# STLINKV2-1.net
KiCad netlist of a schematic drawn in Altium Designer
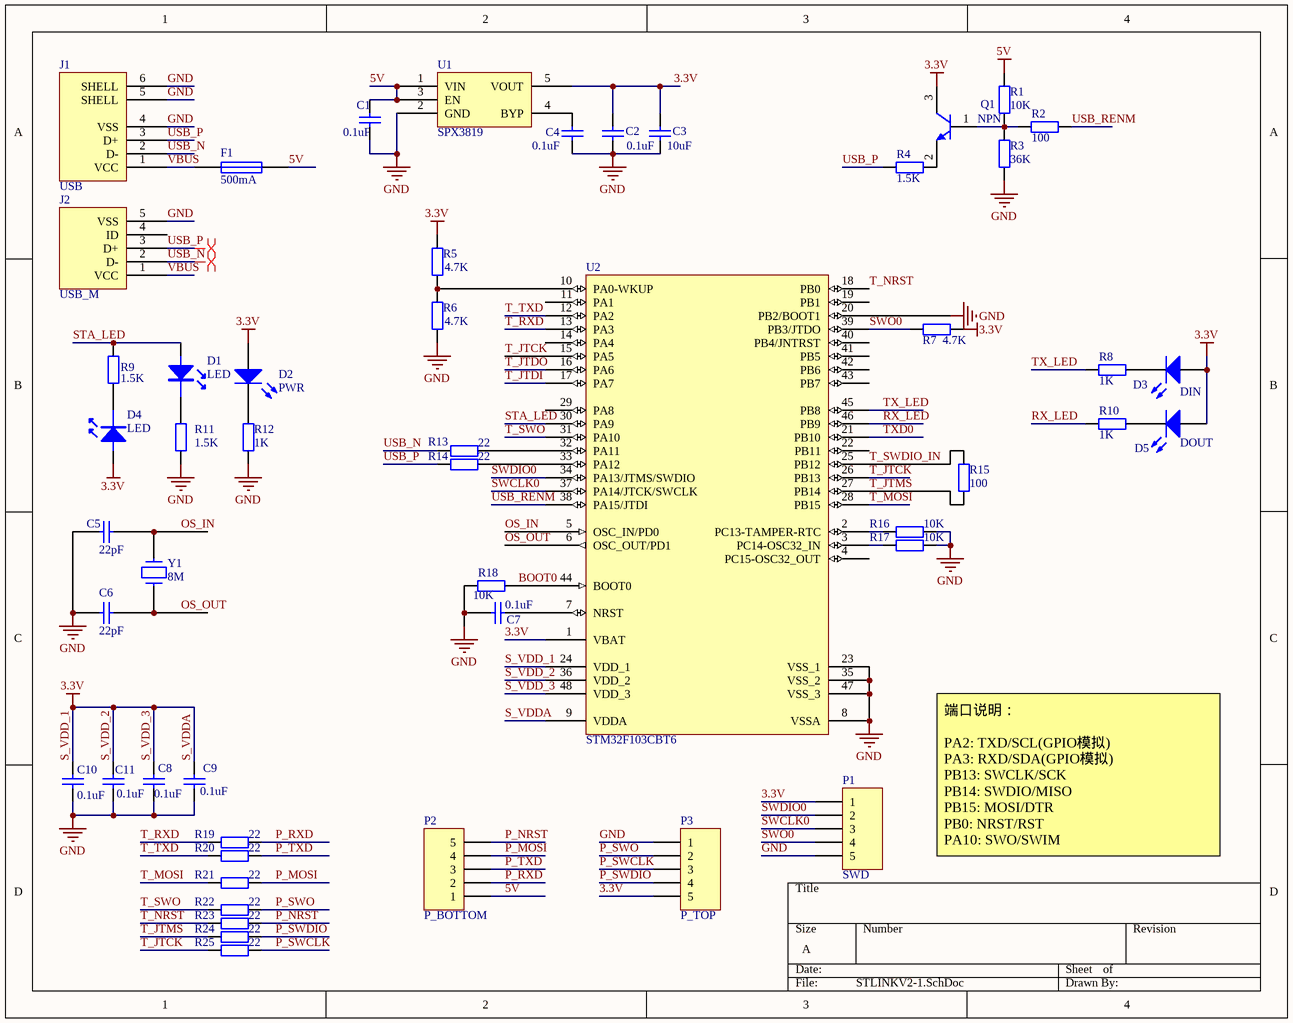
[diagram p0: STLINKV2-1.SchDoc]

(export (version "E")
  (design (tool "Eeschema 10.0.6"))
  (components
    (comp (ref "C1")
      (value "0.1uF")
      (footprint "C-0603")
      (description "Capacitor")
      (fields (field (name "Comment") "Cap") (field (name "PUBLISHER") "Altium Limited"))
      (libsource (lib "Miscellaneous Devices") (part "Cap"))
    )
    (comp (ref "C2")
      (value "0.1uF")
      (footprint "C-0603")
      (description "Capacitor")
      (fields (field (name "Comment") "Cap") (field (name "PUBLISHER") "Altium Limited"))
      (libsource (lib "Miscellaneous Devices") (part "Cap"))
    )
    (comp (ref "C3")
      (value "10uF")
      (footprint "C-0603")
      (description "Capacitor")
      (fields (field (name "Comment") "Cap") (field (name "PUBLISHER") "Altium Limited"))
      (libsource (lib "Miscellaneous Devices") (part "Cap"))
    )
    (comp (ref "C4")
      (value "0.1uF")
      (footprint "C-0603")
      (description "Capacitor")
      (fields (field (name "Comment") "Cap") (field (name "PUBLISHER") "Altium Limited"))
      (libsource (lib "Miscellaneous Devices") (part "Cap"))
    )
    (comp (ref "C5")
      (value "22pF")
      (footprint "C-0603")
      (fields (field (name "Comment") "Cap"))
      (libsource (lib "WK_PCB") (part "Cap"))
    )
    (comp (ref "C6")
      (value "22pF")
      (footprint "C-0603")
      (fields (field (name "Comment") "Cap"))
      (libsource (lib "WK_PCB") (part "Cap"))
    )
    (comp (ref "C7")
      (value "0.1uF")
      (footprint "C-0603")
      (fields (field (name "Comment") "Cap"))
      (libsource (lib "WK_PCB") (part "Cap"))
    )
    (comp (ref "C8")
      (value "0.1uF")
      (footprint "C-0603")
      (description "Capacitor")
      (fields (field (name "Comment") "Cap") (field (name "PUBLISHER") "Altium Limited"))
      (libsource (lib "Miscellaneous Devices") (part "Cap"))
    )
    (comp (ref "C9")
      (value "0.1uF")
      (footprint "C-0603")
      (description "Capacitor")
      (fields (field (name "Comment") "Cap") (field (name "PUBLISHER") "Altium Limited"))
      (libsource (lib "Miscellaneous Devices") (part "Cap"))
    )
    (comp (ref "C10")
      (value "0.1uF")
      (footprint "C-0603")
      (description "Capacitor")
      (fields (field (name "Comment") "Cap") (field (name "PUBLISHER") "Altium Limited"))
      (libsource (lib "Miscellaneous Devices") (part "Cap"))
    )
    (comp (ref "C11")
      (value "0.1uF")
      (footprint "C-0603")
      (description "Capacitor")
      (fields (field (name "Comment") "Cap") (field (name "PUBLISHER") "Altium Limited"))
      (libsource (lib "Miscellaneous Devices") (part "Cap"))
    )
    (comp (ref "D1")
      (value "LED")
      (footprint "SMT_LED_0603")
      (description "LED 发光二极管")
      (libsource (lib "WK_PCB") (part "LED"))
    )
    (comp (ref "D2")
      (value "PWR")
      (footprint "SMT_LED_0603")
      (description "Typical RED, GREEN, YELLOW, AMBER GaAs LED")
      (fields (field (name "PUBLISHER") "Altium Limited"))
      (libsource (lib "Miscellaneous Devices") (part "LED2"))
    )
    (comp (ref "D3")
      (value "DIN")
      (footprint "SMT_LED_0603")
      (description "Typical RED, GREEN, YELLOW, AMBER GaAs LED")
      (fields (field (name "PUBLISHER") "Altium Limited"))
      (libsource (lib "Miscellaneous Devices") (part "LED2"))
    )
    (comp (ref "D4")
      (value "LED")
      (footprint "SMT_LED_0603")
      (description "LED 发光二极管")
      (libsource (lib "WK_PCB") (part "LED"))
    )
    (comp (ref "D5")
      (value "DOUT")
      (footprint "SMT_LED_0603")
      (description "Typical RED, GREEN, YELLOW, AMBER GaAs LED")
      (fields (field (name "PUBLISHER") "Altium Limited"))
      (libsource (lib "Miscellaneous Devices") (part "LED2"))
    )
    (comp (ref "F1")
      (value "500mA")
      (footprint "0805-1")
      (description "保险丝")
      (fields (field (name "Comment") "Fuse1"))
      (libsource (lib "Fszhang") (part "Fuse1"))
    )
    (comp (ref "J1")
      (value "USB")
      (footprint "USB-B")
      (description "USB接口")
      (libsource (lib "HDR_Fszhang") (part "USB"))
    )
    (comp (ref "J2")
      (value "USB_M")
      (footprint "USB_MICRO_5S_B")
      (description "Micro/Mini USB")
      (libsource (lib "HDR_Fszhang") (part "USB_M"))
    )
    (comp (ref "P1")
      (value "SWD")
      (footprint "SIP5-1.27")
      (description "Header, 5-Pin")
      (fields (field (name "PUBLISHER") "Altium Limited"))
      (libsource (lib "") (part "Header 5_1"))
    )
    (comp (ref "P2")
      (value "P_BOTTOM")
      (footprint "HEADER 5")
      (description "Header, 5-Pin")
      (fields (field (name "PUBLISHER") "Altium Limited"))
      (libsource (lib "Miscellaneous Connectors") (part "Header 5"))
    )
    (comp (ref "P3")
      (value "P_TOP")
      (footprint "HEADER 5")
      (description "Header, 5-Pin")
      (fields (field (name "PUBLISHER") "Altium Limited"))
      (libsource (lib "") (part "Header 5_1"))
    )
    (comp (ref "Q1")
      (value "NPN")
      (footprint "SOT23-3")
      (description "贴片三极管")
      (fields (field (name "PUBLISHER") "Altium Limited"))
      (libsource (lib "Fszhang") (part "NPN1"))
    )
    (comp (ref "R1")
      (value "10K")
      (footprint "0603-1")
      (description "贴片电阻")
      (fields (field (name "Comment") "Res1") (field (name "PUBLISHER") "Altium Limited"))
      (libsource (lib "Fszhang") (part "Res1"))
    )
    (comp (ref "R2")
      (value "100")
      (footprint "0603-1")
      (description "贴片电阻")
      (fields (field (name "Comment") "Res1") (field (name "PUBLISHER") "Altium Limited"))
      (libsource (lib "") (part "Res1_1"))
    )
    (comp (ref "R3")
      (value "36K")
      (footprint "0603-1")
      (description "贴片电阻")
      (fields (field (name "Comment") "Res1") (field (name "PUBLISHER") "Altium Limited"))
      (libsource (lib "Fszhang") (part "Res1"))
    )
    (comp (ref "R4")
      (value "1.5K")
      (footprint "0603-1")
      (description "贴片电阻")
      (fields (field (name "Comment") "Res1") (field (name "PUBLISHER") "Altium Limited"))
      (libsource (lib "") (part "Res1_2"))
    )
    (comp (ref "R5")
      (value "4.7K")
      (footprint "0603-1")
      (description "Resistor")
      (fields (field (name "Comment") "Res2") (field (name "PUBLISHER") "Altium Limited"))
      (libsource (lib "") (part "Res2_1"))
    )
    (comp (ref "R6")
      (value "4.7K")
      (footprint "0603-1")
      (description "Resistor")
      (fields (field (name "Comment") "Res2") (field (name "PUBLISHER") "Altium Limited"))
      (libsource (lib "") (part "Res2_1"))
    )
    (comp (ref "R7")
      (value "4.7K")
      (footprint "0603-1")
      (description "Resistor")
      (fields (field (name "Comment") "Res2") (field (name "PUBLISHER") "Altium Limited"))
      (libsource (lib "Miscellaneous Devices") (part "Res2"))
    )
    (comp (ref "R8")
      (value "1K")
      (footprint "0603-1")
      (description "Resistor")
      (fields (field (name "Comment") "Res2") (field (name "PUBLISHER") "Altium Limited"))
      (libsource (lib "Miscellaneous Devices") (part "Res2"))
    )
    (comp (ref "R9")
      (value "1.5K")
      (footprint "0603-1")
      (description "Resistor")
      (fields (field (name "Comment") "Res2") (field (name "PUBLISHER") "Altium Limited"))
      (libsource (lib "") (part "Res2_1"))
    )
    (comp (ref "R10")
      (value "1K")
      (footprint "0603-1")
      (description "Resistor")
      (fields (field (name "Comment") "Res2") (field (name "PUBLISHER") "Altium Limited"))
      (libsource (lib "Miscellaneous Devices") (part "Res2"))
    )
    (comp (ref "R11")
      (value "1.5K")
      (footprint "0603-1")
      (description "Resistor")
      (fields (field (name "Comment") "Res2") (field (name "PUBLISHER") "Altium Limited"))
      (libsource (lib "") (part "Res2_1"))
    )
    (comp (ref "R12")
      (value "1K")
      (footprint "0603-1")
      (description "Resistor")
      (fields (field (name "Comment") "Res2") (field (name "PUBLISHER") "Altium Limited"))
      (libsource (lib "") (part "Res2_1"))
    )
    (comp (ref "R13")
      (value "22")
      (footprint "0603-1")
      (description "Resistor")
      (fields (field (name "Comment") "Res2") (field (name "PUBLISHER") "Altium Limited"))
      (libsource (lib "Miscellaneous Devices") (part "Res2"))
    )
    (comp (ref "R14")
      (value "22")
      (footprint "0603-1")
      (description "Resistor")
      (fields (field (name "Comment") "Res2") (field (name "PUBLISHER") "Altium Limited"))
      (libsource (lib "Miscellaneous Devices") (part "Res2"))
    )
    (comp (ref "R15")
      (value "100")
      (footprint "0603-1")
      (description "Resistor")
      (fields (field (name "Comment") "Res2") (field (name "PUBLISHER") "Altium Limited"))
      (libsource (lib "") (part "Res2_1"))
    )
    (comp (ref "R16")
      (value "10K")
      (footprint "0603-1")
      (description "贴片电阻")
      (fields (field (name "Comment") "Res1") (field (name "PUBLISHER") "Altium Limited"))
      (libsource (lib "") (part "Res1_1"))
    )
    (comp (ref "R17")
      (value "10K")
      (footprint "0603-1")
      (description "贴片电阻")
      (fields (field (name "Comment") "Res1") (field (name "PUBLISHER") "Altium Limited"))
      (libsource (lib "") (part "Res1_1"))
    )
    (comp (ref "R18")
      (value "10K")
      (footprint "0603-1")
      (description "Resistor")
      (fields (field (name "Comment") "Res2") (field (name "PUBLISHER") "Altium Limited"))
      (libsource (lib "Miscellaneous Devices") (part "Res2"))
    )
    (comp (ref "R19")
      (value "22")
      (footprint "0603-1")
      (description "Resistor")
      (fields (field (name "Comment") "Res2") (field (name "PUBLISHER") "Altium Limited"))
      (libsource (lib "Miscellaneous Devices") (part "Res2"))
    )
    (comp (ref "R20")
      (value "22")
      (footprint "0603-1")
      (description "Resistor")
      (fields (field (name "Comment") "Res2") (field (name "PUBLISHER") "Altium Limited"))
      (libsource (lib "Miscellaneous Devices") (part "Res2"))
    )
    (comp (ref "R21")
      (value "22")
      (footprint "0603-1")
      (description "Resistor")
      (fields (field (name "Comment") "Res2") (field (name "PUBLISHER") "Altium Limited"))
      (libsource (lib "Miscellaneous Devices") (part "Res2"))
    )
    (comp (ref "R22")
      (value "22")
      (footprint "0603-1")
      (description "Resistor")
      (fields (field (name "Comment") "Res2") (field (name "PUBLISHER") "Altium Limited"))
      (libsource (lib "Miscellaneous Devices") (part "Res2"))
    )
    (comp (ref "R23")
      (value "22")
      (footprint "0603-1")
      (description "Resistor")
      (fields (field (name "Comment") "Res2") (field (name "PUBLISHER") "Altium Limited"))
      (libsource (lib "Miscellaneous Devices") (part "Res2"))
    )
    (comp (ref "R24")
      (value "22")
      (footprint "0603-1")
      (description "Resistor")
      (fields (field (name "Comment") "Res2") (field (name "PUBLISHER") "Altium Limited"))
      (libsource (lib "Miscellaneous Devices") (part "Res2"))
    )
    (comp (ref "R25")
      (value "22")
      (footprint "0603-1")
      (description "Resistor")
      (fields (field (name "Comment") "Res2") (field (name "PUBLISHER") "Altium Limited"))
      (libsource (lib "Miscellaneous Devices") (part "Res2"))
    )
    (comp (ref "U1") (value "SPX3819") (footprint "SOT23-5") (libsource (lib "Schlib1") (part "SPX3819")))
    (comp (ref "U2")
      (value "STM32F103CBT6")
      (footprint "LQFP48_N")
      (description "STM32 ARM-based 32-bit MCU with 64 Kbytes Flash, 48-pin LQFP, Industrial Temperature")
      (fields (field (name "PUBLISHER") "Altium Limited"))
      (libsource (lib "ST Microcontroller 32-Bit STM32") (part "STM32F103C8T6"))
    )
    (comp (ref "Y1") (value "8M") (footprint "XAL5032 2-Leads") (libsource (lib "WK_PCB") (part "XTAL")))
  )
  (nets
    (net (code "1") (name "/BOOT0") (class "Default")
      (node (ref "R18") (pin "2") (pinfunction "2_2") (pintype "passive"))
      (node (ref "U2") (pin "44") (pinfunction "BOOT0_44") (pintype "input"))
    )
    (net (code "2") (name "/OS_IN") (class "Default")
      (node (ref "C5") (pin "2") (pinfunction "2_2") (pintype "passive"))
      (node (ref "U2") (pin "5") (pinfunction "OSC_IN/PD0_5") (pintype "input"))
      (node (ref "Y1") (pin "2") (pinfunction "2_2") (pintype "passive"))
    )
    (net (code "3") (name "/OS_OUT") (class "Default")
      (node (ref "C6") (pin "2") (pinfunction "2_2") (pintype "passive"))
      (node (ref "U2") (pin "6") (pinfunction "OSC_OUT/PD1_6") (pintype "output"))
      (node (ref "Y1") (pin "1") (pinfunction "1_1") (pintype "passive"))
    )
    (net (code "4") (name "/P_MOSI") (class "Default")
      (node (ref "P2") (pin "4") (pinfunction "4_4") (pintype "passive"))
      (node (ref "R21") (pin "2") (pinfunction "2_2") (pintype "passive"))
    )
    (net (code "5") (name "/P_NRST") (class "Default")
      (node (ref "P2") (pin "5") (pinfunction "5_5") (pintype "passive"))
      (node (ref "R23") (pin "2") (pinfunction "2_2") (pintype "passive"))
    )
    (net (code "6") (name "/P_RXD") (class "Default")
      (node (ref "P2") (pin "2") (pinfunction "2_2") (pintype "passive"))
      (node (ref "R19") (pin "2") (pinfunction "2_2") (pintype "passive"))
    )
    (net (code "7") (name "/P_SWCLK") (class "Default")
      (node (ref "P3") (pin "3") (pinfunction "3_3") (pintype "passive"))
      (node (ref "R25") (pin "2") (pinfunction "2_2") (pintype "passive"))
    )
    (net (code "8") (name "/P_SWDIO") (class "Default")
      (node (ref "P3") (pin "4") (pinfunction "4_4") (pintype "passive"))
      (node (ref "R24") (pin "2") (pinfunction "2_2") (pintype "passive"))
    )
    (net (code "9") (name "/P_SWO") (class "Default")
      (node (ref "P3") (pin "2") (pinfunction "2_2") (pintype "passive"))
      (node (ref "R22") (pin "2") (pinfunction "2_2") (pintype "passive"))
    )
    (net (code "10") (name "/P_TXD") (class "Default")
      (node (ref "P2") (pin "3") (pinfunction "3_3") (pintype "passive"))
      (node (ref "R20") (pin "2") (pinfunction "2_2") (pintype "passive"))
    )
    (net (code "11") (name "/RX_LED") (class "Default")
      (node (ref "R10") (pin "1") (pinfunction "1_1") (pintype "passive"))
      (node (ref "U2") (pin "46") (pinfunction "PB9_46") (pintype "bidirectional"))
    )
    (net (code "12") (name "/STA_LED") (class "Default")
      (node (ref "D1") (pin "1") (pinfunction "A_1") (pintype "passive"))
      (node (ref "R9") (pin "2") (pinfunction "2_2") (pintype "passive"))
      (node (ref "U2") (pin "30") (pinfunction "PA9_30") (pintype "bidirectional"))
    )
    (net (code "13") (name "/SWCLK0") (class "Default")
      (node (ref "P1") (pin "3") (pinfunction "3_3") (pintype "passive"))
      (node (ref "U2") (pin "37") (pinfunction "PA14/JTCK/SWCLK_37") (pintype "bidirectional"))
    )
    (net (code "14") (name "/SWDIO0") (class "Default")
      (node (ref "P1") (pin "2") (pinfunction "2_2") (pintype "passive"))
      (node (ref "U2") (pin "34") (pinfunction "PA13/JTMS/SWDIO_34") (pintype "bidirectional"))
    )
    (net (code "15") (name "/SWO0") (class "Default")
      (node (ref "P1") (pin "4") (pinfunction "4_4") (pintype "passive"))
      (node (ref "R7") (pin "1") (pinfunction "1_1") (pintype "passive"))
      (node (ref "U2") (pin "39") (pinfunction "PB3/JTDO_39") (pintype "bidirectional"))
    )
    (net (code "16") (name "/TXD0") (class "Default")
      (node (ref "U2") (pin "21") (pinfunction "PB10_21") (pintype "bidirectional"))
    )
    (net (code "17") (name "/TX_LED") (class "Default")
      (node (ref "R8") (pin "1") (pinfunction "1_1") (pintype "passive"))
      (node (ref "U2") (pin "45") (pinfunction "PB8_45") (pintype "bidirectional"))
    )
    (net (code "18") (name "/T_JTCK") (class "Default")
      (node (ref "R25") (pin "1") (pinfunction "1_1") (pintype "passive"))
      (node (ref "U2") (pin "15") (pinfunction "PA5_15") (pintype "bidirectional"))
      (node (ref "U2") (pin "26") (pinfunction "PB13_26") (pintype "bidirectional"))
    )
    (net (code "19") (name "/T_JTDI") (class "Default")
      (node (ref "U2") (pin "17") (pinfunction "PA7_17") (pintype "bidirectional"))
    )
    (net (code "20") (name "/T_JTDO") (class "Default")
      (node (ref "U2") (pin "16") (pinfunction "PA6_16") (pintype "bidirectional"))
    )
    (net (code "21") (name "/T_JTMS") (class "Default")
      (node (ref "R15") (pin "1") (pinfunction "1_1") (pintype "passive"))
      (node (ref "R24") (pin "1") (pinfunction "1_1") (pintype "passive"))
      (node (ref "U2") (pin "27") (pinfunction "PB14_27") (pintype "bidirectional"))
    )
    (net (code "22") (name "/T_MOSI") (class "Default")
      (node (ref "R21") (pin "1") (pinfunction "1_1") (pintype "passive"))
      (node (ref "U2") (pin "28") (pinfunction "PB15_28") (pintype "bidirectional"))
    )
    (net (code "23") (name "/T_NRST") (class "Default")
      (node (ref "R23") (pin "1") (pinfunction "1_1") (pintype "passive"))
      (node (ref "U2") (pin "18") (pinfunction "PB0_18") (pintype "bidirectional"))
    )
    (net (code "24") (name "/T_RXD") (class "Default")
      (node (ref "R19") (pin "1") (pinfunction "1_1") (pintype "passive"))
      (node (ref "U2") (pin "13") (pinfunction "PA3_13") (pintype "bidirectional"))
    )
    (net (code "25") (name "/T_SWDIO_IN") (class "Default")
      (node (ref "R15") (pin "2") (pinfunction "2_2") (pintype "passive"))
      (node (ref "U2") (pin "25") (pinfunction "PB12_25") (pintype "bidirectional"))
    )
    (net (code "26") (name "/T_SWO") (class "Default")
      (node (ref "R22") (pin "1") (pinfunction "1_1") (pintype "passive"))
      (node (ref "U2") (pin "31") (pinfunction "PA10_31") (pintype "bidirectional"))
    )
    (net (code "27") (name "/T_TXD") (class "Default")
      (node (ref "R20") (pin "1") (pinfunction "1_1") (pintype "passive"))
      (node (ref "U2") (pin "12") (pinfunction "PA2_12") (pintype "bidirectional"))
    )
    (net (code "28") (name "/USB_N") (class "Default")
      (node (ref "J1") (pin "2") (pinfunction "D-_2") (pintype "passive"))
      (node (ref "J2") (pin "2") (pinfunction "D-_2") (pintype "passive"))
      (node (ref "R13") (pin "1") (pinfunction "1_1") (pintype "passive"))
    )
    (net (code "29") (name "/USB_P") (class "Default")
      (node (ref "J1") (pin "3") (pinfunction "D+_3") (pintype "passive"))
      (node (ref "J2") (pin "3") (pinfunction "D+_3") (pintype "passive"))
      (node (ref "R14") (pin "1") (pinfunction "1_1") (pintype "passive"))
      (node (ref "R4") (pin "2") (pinfunction "2_2") (pintype "passive"))
    )
    (net (code "30") (name "/USB_RENM") (class "Default")
      (node (ref "R2") (pin "2") (pinfunction "2_2") (pintype "passive"))
      (node (ref "U2") (pin "38") (pinfunction "PA15/JTDI_38") (pintype "bidirectional"))
    )
    (net (code "31") (name "/VBUS") (class "Default")
      (node (ref "F1") (pin "2") (pinfunction "2_2") (pintype "passive"))
      (node (ref "J1") (pin "1") (pinfunction "VCC_1") (pintype "passive"))
      (node (ref "J2") (pin "1") (pinfunction "VCC_1") (pintype "passive"))
    )
    (net (code "32") (name "3.3V") (class "Default")
      (node (ref "C10") (pin "2") (pinfunction "2_2") (pintype "passive"))
      (node (ref "C11") (pin "2") (pinfunction "2_2") (pintype "passive"))
      (node (ref "C2") (pin "2") (pinfunction "2_2") (pintype "passive"))
      (node (ref "C3") (pin "2") (pinfunction "2_2") (pintype "passive"))
      (node (ref "C8") (pin "2") (pinfunction "2_2") (pintype "passive"))
      (node (ref "C9") (pin "2") (pinfunction "2_2") (pintype "passive"))
      (node (ref "D2") (pin "1") (pinfunction "A_1") (pintype "passive"))
      (node (ref "D3") (pin "1") (pinfunction "A_1") (pintype "passive"))
      (node (ref "D4") (pin "1") (pinfunction "A_1") (pintype "passive"))
      (node (ref "D5") (pin "1") (pinfunction "A_1") (pintype "passive"))
      (node (ref "P1") (pin "1") (pinfunction "1_1") (pintype "passive"))
      (node (ref "P3") (pin "5") (pinfunction "5_5") (pintype "passive"))
      (node (ref "Q1") (pin "3") (pinfunction "C_3") (pintype "passive"))
      (node (ref "R5") (pin "2") (pinfunction "2_2") (pintype "passive"))
      (node (ref "R7") (pin "2") (pinfunction "2_2") (pintype "passive"))
      (node (ref "U1") (pin "5") (pinfunction "VOUT_5") (pintype "passive"))
      (node (ref "U2") (pin "1") (pinfunction "VBAT_1") (pintype "power_in"))
      (node (ref "U2") (pin "24") (pinfunction "VDD_1_24") (pintype "power_in"))
      (node (ref "U2") (pin "36") (pinfunction "VDD_2_36") (pintype "power_in"))
      (node (ref "U2") (pin "48") (pinfunction "VDD_3_48") (pintype "power_in"))
      (node (ref "U2") (pin "9") (pinfunction "VDDA_9") (pintype "power_in"))
    )
    (net (code "33") (name "5V") (class "Default")
      (node (ref "C1") (pin "2") (pinfunction "2_2") (pintype "passive"))
      (node (ref "F1") (pin "1") (pinfunction "1_1") (pintype "passive"))
      (node (ref "P2") (pin "1") (pinfunction "1_1") (pintype "passive"))
      (node (ref "R1") (pin "1") (pinfunction "1_1") (pintype "passive"))
      (node (ref "U1") (pin "1") (pinfunction "VIN_1") (pintype "passive"))
      (node (ref "U1") (pin "3") (pinfunction "EN_3") (pintype "passive"))
    )
    (net (code "34") (name "GND") (class "Default")
      (node (ref "C1") (pin "1") (pinfunction "1_1") (pintype "passive"))
      (node (ref "C10") (pin "1") (pinfunction "1_1") (pintype "passive"))
      (node (ref "C11") (pin "1") (pinfunction "1_1") (pintype "passive"))
      (node (ref "C2") (pin "1") (pinfunction "1_1") (pintype "passive"))
      (node (ref "C3") (pin "1") (pinfunction "1_1") (pintype "passive"))
      (node (ref "C4") (pin "1") (pinfunction "1_1") (pintype "passive"))
      (node (ref "C5") (pin "1") (pinfunction "1_1") (pintype "passive"))
      (node (ref "C6") (pin "1") (pinfunction "1_1") (pintype "passive"))
      (node (ref "C7") (pin "1") (pinfunction "1_1") (pintype "passive"))
      (node (ref "C8") (pin "1") (pinfunction "1_1") (pintype "passive"))
      (node (ref "C9") (pin "1") (pinfunction "1_1") (pintype "passive"))
      (node (ref "J1") (pin "4") (pinfunction "VSS_4") (pintype "passive"))
      (node (ref "J1") (pin "5") (pinfunction "SHELL_5") (pintype "passive"))
      (node (ref "J1") (pin "6") (pinfunction "SHELL_6") (pintype "passive"))
      (node (ref "J2") (pin "5") (pinfunction "VSS_5") (pintype "passive"))
      (node (ref "P1") (pin "5") (pinfunction "5_5") (pintype "passive"))
      (node (ref "P3") (pin "1") (pinfunction "1_1") (pintype "passive"))
      (node (ref "R11") (pin "1") (pinfunction "1_1") (pintype "passive"))
      (node (ref "R12") (pin "1") (pinfunction "1_1") (pintype "passive"))
      (node (ref "R16") (pin "2") (pinfunction "2_2") (pintype "passive"))
      (node (ref "R17") (pin "2") (pinfunction "2_2") (pintype "passive"))
      (node (ref "R18") (pin "1") (pinfunction "1_1") (pintype "passive"))
      (node (ref "R3") (pin "2") (pinfunction "2_2") (pintype "passive"))
      (node (ref "R6") (pin "1") (pinfunction "1_1") (pintype "passive"))
      (node (ref "U1") (pin "2") (pinfunction "GND_2") (pintype "passive"))
      (node (ref "U2") (pin "20") (pinfunction "PB2/BOOT1_20") (pintype "bidirectional"))
      (node (ref "U2") (pin "23") (pinfunction "VSS_1_23") (pintype "power_in"))
      (node (ref "U2") (pin "35") (pinfunction "VSS_2_35") (pintype "power_in"))
      (node (ref "U2") (pin "47") (pinfunction "VSS_3_47") (pintype "power_in"))
      (node (ref "U2") (pin "8") (pinfunction "VSSA_8") (pintype "power_in"))
    )
    (net (code "35") (name "Net-(D1-K)") (class "Default")
      (node (ref "D1") (pin "2") (pinfunction "K_2") (pintype "passive"))
      (node (ref "R11") (pin "2") (pinfunction "2_2") (pintype "passive"))
    )
    (net (code "36") (name "Net-(D2-K)") (class "Default")
      (node (ref "D2") (pin "2") (pinfunction "K_2") (pintype "passive"))
      (node (ref "R12") (pin "2") (pinfunction "2_2") (pintype "passive"))
    )
    (net (code "37") (name "Net-(D3-K)") (class "Default")
      (node (ref "D3") (pin "2") (pinfunction "K_2") (pintype "passive"))
      (node (ref "R8") (pin "2") (pinfunction "2_2") (pintype "passive"))
    )
    (net (code "38") (name "Net-(D4-K)") (class "Default")
      (node (ref "D4") (pin "2") (pinfunction "K_2") (pintype "passive"))
      (node (ref "R9") (pin "1") (pinfunction "1_1") (pintype "passive"))
    )
    (net (code "39") (name "Net-(D5-K)") (class "Default")
      (node (ref "D5") (pin "2") (pinfunction "K_2") (pintype "passive"))
      (node (ref "R10") (pin "2") (pinfunction "2_2") (pintype "passive"))
    )
    (net (code "40") (name "Net-(Q1-B)") (class "Default")
      (node (ref "Q1") (pin "1") (pinfunction "B_1") (pintype "passive"))
      (node (ref "R1") (pin "2") (pinfunction "2_2") (pintype "passive"))
      (node (ref "R2") (pin "1") (pinfunction "1_1") (pintype "passive"))
      (node (ref "R3") (pin "1") (pinfunction "1_1") (pintype "passive"))
    )
    (net (code "41") (name "Net-(Q1-E)") (class "Default")
      (node (ref "Q1") (pin "2") (pinfunction "E_2") (pintype "passive"))
      (node (ref "R4") (pin "1") (pinfunction "1_1") (pintype "passive"))
    )
    (net (code "42") (name "Net-(U1-BYP)") (class "Default")
      (node (ref "C4") (pin "2") (pinfunction "2_2") (pintype "passive"))
      (node (ref "U1") (pin "4") (pinfunction "BYP_4") (pintype "passive"))
    )
    (net (code "43") (name "Net-(U2-NRST)") (class "Default")
      (node (ref "C7") (pin "2") (pinfunction "2_2") (pintype "passive"))
      (node (ref "U2") (pin "7") (pinfunction "NRST_7") (pintype "bidirectional"))
    )
    (net (code "44") (name "Net-(U2-PA0-WKUP)") (class "Default")
      (node (ref "R5") (pin "1") (pinfunction "1_1") (pintype "passive"))
      (node (ref "R6") (pin "2") (pinfunction "2_2") (pintype "passive"))
      (node (ref "U2") (pin "10") (pinfunction "PA0-WKUP_10") (pintype "bidirectional"))
    )
    (net (code "45") (name "Net-(U2-PA11)") (class "Default")
      (node (ref "R13") (pin "2") (pinfunction "2_2") (pintype "passive"))
      (node (ref "U2") (pin "32") (pinfunction "PA11_32") (pintype "bidirectional"))
    )
    (net (code "46") (name "Net-(U2-PA12)") (class "Default")
      (node (ref "R14") (pin "2") (pinfunction "2_2") (pintype "passive"))
      (node (ref "U2") (pin "33") (pinfunction "PA12_33") (pintype "bidirectional"))
    )
    (net (code "47") (name "Net-(U2-PC13-TAMPER-RTC)") (class "Default")
      (node (ref "R16") (pin "1") (pinfunction "1_1") (pintype "passive"))
      (node (ref "U2") (pin "2") (pinfunction "PC13-TAMPER-RTC_2") (pintype "bidirectional"))
    )
    (net (code "48") (name "Net-(U2-PC14-OSC32_IN)") (class "Default")
      (node (ref "R17") (pin "1") (pinfunction "1_1") (pintype "passive"))
      (node (ref "U2") (pin "3") (pinfunction "PC14-OSC32_IN_3") (pintype "bidirectional"))
    )
    (net (code "49") (name "unconnected-(J2-ID-Pad4)") (class "Default")
      (node (ref "J2") (pin "4") (pinfunction "ID_4") (pintype "passive"))
    )
    (net (code "50") (name "unconnected-(U2-PA1-Pad11)") (class "Default")
      (node (ref "U2") (pin "11") (pinfunction "PA1_11") (pintype "bidirectional"))
    )
    (net (code "51") (name "unconnected-(U2-PA4-Pad14)") (class "Default")
      (node (ref "U2") (pin "14") (pinfunction "PA4_14") (pintype "bidirectional"))
    )
    (net (code "52") (name "unconnected-(U2-PA8-Pad29)") (class "Default")
      (node (ref "U2") (pin "29") (pinfunction "PA8_29") (pintype "bidirectional"))
    )
    (net (code "53") (name "unconnected-(U2-PB1-Pad19)") (class "Default")
      (node (ref "U2") (pin "19") (pinfunction "PB1_19") (pintype "bidirectional"))
    )
    (net (code "54") (name "unconnected-(U2-PB4{slash}JNTRST-Pad40)") (class "Default")
      (node (ref "U2") (pin "40") (pinfunction "PB4/JNTRST_40") (pintype "bidirectional"))
    )
    (net (code "55") (name "unconnected-(U2-PB5-Pad41)") (class "Default")
      (node (ref "U2") (pin "41") (pinfunction "PB5_41") (pintype "bidirectional"))
    )
    (net (code "56") (name "unconnected-(U2-PB6-Pad42)") (class "Default")
      (node (ref "U2") (pin "42") (pinfunction "PB6_42") (pintype "bidirectional"))
    )
    (net (code "57") (name "unconnected-(U2-PB7-Pad43)") (class "Default")
      (node (ref "U2") (pin "43") (pinfunction "PB7_43") (pintype "bidirectional"))
    )
    (net (code "58") (name "unconnected-(U2-PB11-Pad22)") (class "Default")
      (node (ref "U2") (pin "22") (pinfunction "PB11_22") (pintype "bidirectional"))
    )
    (net (code "59") (name "unconnected-(U2-PC15-OSC32_OUT-Pad4)") (class "Default")
      (node (ref "U2") (pin "4") (pinfunction "PC15-OSC32_OUT_4") (pintype "bidirectional"))
    )
  )
)
